# WIFI.net
KiCad netlist of a schematic drawn in Altium Designer
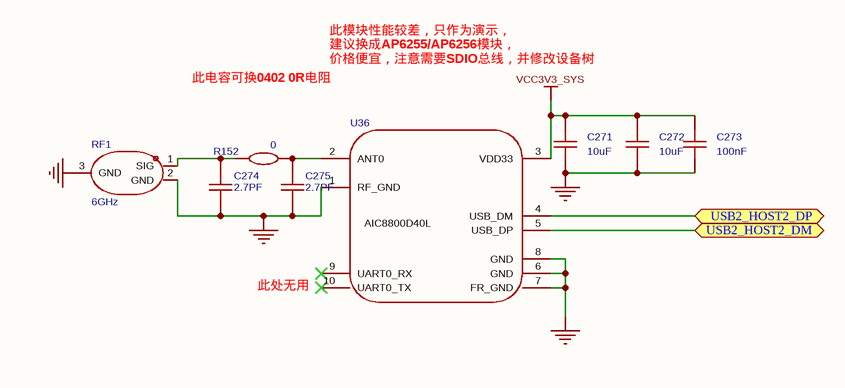
[diagram p0: WIFI.schdoc]

(export (version "E")
  (design (tool "Eeschema 10.0.6"))
  (components
    (comp (ref "C271")
      (value "10uF")
      (footprint "C0603")
      (libsource (lib "altium-import") (part "root_1_CAP_0603_"))
    )
    (comp (ref "C272")
      (value "10uF")
      (footprint "C0603")
      (libsource (lib "altium-import") (part "root_1_CAP_0603_"))
    )
    (comp (ref "C273")
      (value "100nF")
      (footprint "C0603")
      (libsource (lib "altium-import") (part "root_1_CAP_0603_"))
    )
    (comp (ref "C274")
      (value "2.7PF")
      (footprint "MYC0402")
      (libsource (lib "altium-import") (part "root_1_CAP_0402_"))
    )
    (comp (ref "C275")
      (value "2.7PF")
      (footprint "MYC0402")
      (libsource (lib "altium-import") (part "root_1_CAP_0402_"))
    )
    (comp (ref "R152")
      (value "0")
      (footprint "R0402")
      (libsource (lib "altium-import") (part "root_0_Res_0402_"))
    )
    (comp (ref "RF1")
      (value "6GHz")
      (footprint "IPEX-SMD_BWIPX-1-001E")
      (description "连接器类型:板端;接口类型:内针;端口数量:1;接口直径:-;接口长度/高度:-;频率:6GHz;射频系列:IPEX;阻抗:50Ω;样式:-;工作温度:-;")
      (fields
        (field (name "MANUFACTURER") "BAT WIRELESS(蝙蝠无线)")
        (field (name "MANUFACTURERPART") "BWIPX-1-001E")
      )
      (libsource (lib "altium-import") (part "root_0_mirrored_BWIPX-1-001E_"))
    )
    (comp (ref "U36")
      (value "~")
      (footprint "BL_M8800DU6_40L")
      (description "AIC8800D40L双频5G无线模块wifi6+BLE蓝牙配网IPC摄像头投屏图传")
      (libsource (lib "altium-import") (part "root_0_BL_M8800DU6_40L_"))
    )
  )
  (nets
    (net (code "1") (name "/USB2_HOST2_DM") (class "Default")
      (node (ref "U36") (pin "5") (pinfunction "USB_DP_5") (pintype "passive"))
    )
    (net (code "2") (name "/USB2_HOST2_DP") (class "Default")
      (node (ref "U36") (pin "4") (pinfunction "USB_DM_4") (pintype "passive"))
    )
    (net (code "3") (name "GND") (class "Default")
      (node (ref "C271") (pin "1") (pinfunction "1_1") (pintype "passive"))
      (node (ref "C272") (pin "1") (pinfunction "1_1") (pintype "passive"))
      (node (ref "C273") (pin "1") (pinfunction "1_1") (pintype "passive"))
      (node (ref "C274") (pin "1") (pinfunction "1_1") (pintype "passive"))
      (node (ref "C275") (pin "1") (pinfunction "1_1") (pintype "passive"))
      (node (ref "RF1") (pin "2") (pinfunction "GND_2") (pintype "passive"))
      (node (ref "RF1") (pin "3") (pinfunction "GND_3") (pintype "passive"))
      (node (ref "U36") (pin "1") (pinfunction "RF_GND_1") (pintype "passive"))
      (node (ref "U36") (pin "6") (pinfunction "GND_6") (pintype "passive"))
      (node (ref "U36") (pin "7") (pinfunction "FR_GND_7") (pintype "passive"))
      (node (ref "U36") (pin "8") (pinfunction "GND_8") (pintype "passive"))
    )
    (net (code "4") (name "Net-(RF1-SIG)") (class "Default")
      (node (ref "C274") (pin "2") (pinfunction "2_2") (pintype "passive"))
      (node (ref "R152") (pin "1") (pinfunction "1_1") (pintype "passive"))
      (node (ref "RF1") (pin "1") (pinfunction "SIG_1") (pintype "passive"))
    )
    (net (code "5") (name "Net-(U36-ANT0)") (class "Default")
      (node (ref "C275") (pin "2") (pinfunction "2_2") (pintype "passive"))
      (node (ref "R152") (pin "2") (pinfunction "2_2") (pintype "passive"))
      (node (ref "U36") (pin "2") (pinfunction "ANT0_2") (pintype "passive"))
    )
    (net (code "6") (name "VCC3V3_SYS") (class "Default")
      (node (ref "C271") (pin "2") (pinfunction "2_2") (pintype "passive"))
      (node (ref "C272") (pin "2") (pinfunction "2_2") (pintype "passive"))
      (node (ref "C273") (pin "2") (pinfunction "2_2") (pintype "passive"))
      (node (ref "U36") (pin "3") (pinfunction "VDD33_3") (pintype "passive"))
    )
    (net (code "7") (name "unconnected-(U36-UART0_RX-Pad9)") (class "Default")
      (node (ref "U36") (pin "9") (pinfunction "UART0_RX_9") (pintype "passive+no_connect"))
    )
    (net (code "8") (name "unconnected-(U36-UART0_TX-Pad10)") (class "Default")
      (node (ref "U36") (pin "10") (pinfunction "UART0_TX_10") (pintype "passive+no_connect"))
    )
  )
)
